# plantshield_huzzah_2022.net
KiCad netlist of a schematic drawn in EAGLE
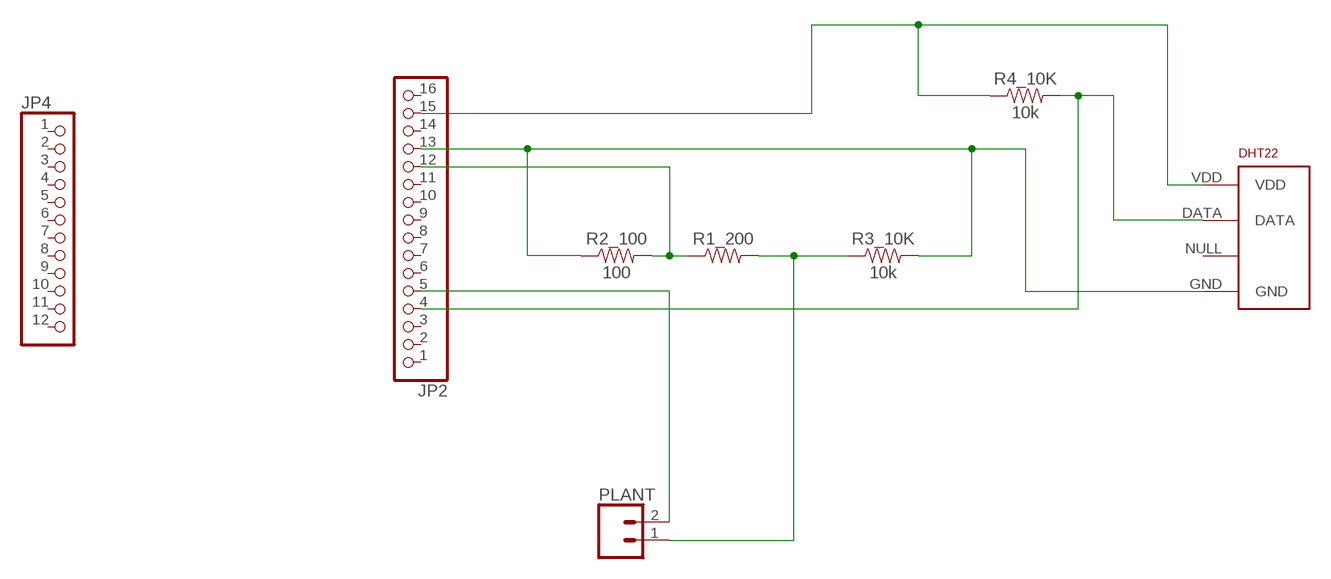
[diagram p0: schematic, sheet 1]

(export (version "E")
  (design (tool "Eeschema 10.0.6"))
  (components
    (comp (ref "DHT22")
      (value "RHT03_DHT-22_AM2302")
      (footprint "eagle-import:RHT03_DHT-22")
      (libsource (lib "eagle-import") (part "RHT03_DHT-22_AM2302"))
    )
    (comp (ref "JP2")
      (value "HEADER-1X16ROUND")
      (footprint "eagle-import:1X16_ROUND")
      (libsource (lib "eagle-import") (part "HEADER-1X16ROUND"))
    )
    (comp (ref "JP4")
      (value "HEADER-1X12")
      (footprint "eagle-import:1X12_ROUND")
      (libsource (lib "eagle-import") (part "HEADER-1X12"))
    )
    (comp (ref "PLANT")
      (value "CONN_02")
      (footprint "eagle-import:1X02")
      (libsource (lib "eagle-import") (part "CONN_02"))
    )
    (comp (ref "R1_200")
      (value "RESISTORAXIAL-0.3")
      (footprint "eagle-import:AXIAL-0.3")
      (libsource (lib "eagle-import") (part "RESISTORAXIAL-0.3"))
    )
    (comp (ref "R2_100")
      (value "100")
      (footprint "eagle-import:AXIAL-0.3")
      (libsource (lib "eagle-import") (part "100OHM-HORIZ-1/4W-1%"))
    )
    (comp (ref "R3_10K")
      (value "10k")
      (footprint "eagle-import:AXIAL-0.3")
      (libsource (lib "eagle-import") (part "10KOHM-HORIZ-1/4W-1%"))
    )
    (comp (ref "R4_10K")
      (value "10k")
      (footprint "eagle-import:AXIAL-0.3")
      (libsource (lib "eagle-import") (part "10KOHM-HORIZ-1/4W-1%"))
    )
  )
  (nets
    (net (code "1") (name "Net-(JP2-Pad5)") (class "Default")
      (node (ref "JP2") (pin "5") (pinfunction "5_5") (pintype "passive"))
      (node (ref "PLANT") (pin "2") (pinfunction "2_2") (pintype "passive"))
    )
    (net (code "2") (name "Net-(R1_200-1)") (class "Default")
      (node (ref "JP2") (pin "12") (pinfunction "12_12") (pintype "passive"))
      (node (ref "R1_200") (pin "P$1") (pinfunction "1_P$1") (pintype "passive"))
      (node (ref "R2_100") (pin "P$2") (pinfunction "2_P$2") (pintype "passive"))
    )
    (net (code "3") (name "Net-(R1_200-2)") (class "Default")
      (node (ref "PLANT") (pin "1") (pinfunction "1_1") (pintype "passive"))
      (node (ref "R1_200") (pin "P$2") (pinfunction "2_P$2") (pintype "passive"))
      (node (ref "R3_10K") (pin "P$1") (pinfunction "1_P$1") (pintype "passive"))
    )
    (net (code "4") (name "Net-(R2_100-1)") (class "Default")
      (node (ref "DHT22") (pin "GND") (pinfunction "GND_GND") (pintype "power_in"))
      (node (ref "JP2") (pin "13") (pinfunction "13_13") (pintype "passive"))
      (node (ref "R2_100") (pin "P$1") (pinfunction "1_P$1") (pintype "passive"))
      (node (ref "R3_10K") (pin "P$2") (pinfunction "2_P$2") (pintype "passive"))
    )
    (net (code "5") (name "Net-(R4_10K-1)") (class "Default")
      (node (ref "DHT22") (pin "VDD") (pinfunction "VDD_VDD") (pintype "power_in"))
      (node (ref "JP2") (pin "15") (pinfunction "15_15") (pintype "passive"))
      (node (ref "R4_10K") (pin "P$1") (pinfunction "1_P$1") (pintype "passive"))
    )
    (net (code "6") (name "Net-(R4_10K-2)") (class "Default")
      (node (ref "DHT22") (pin "DATA") (pinfunction "DATA_DATA") (pintype "bidirectional"))
      (node (ref "JP2") (pin "4") (pinfunction "4_4") (pintype "passive"))
      (node (ref "R4_10K") (pin "P$2") (pinfunction "2_P$2") (pintype "passive"))
    )
    (net (code "7") (name "unconnected-(DHT22-PadNULL)") (class "Default")
      (node (ref "DHT22") (pin "NULL") (pinfunction "NULL_NULL") (pintype "no_connect"))
    )
    (net (code "8") (name "unconnected-(JP2-Pad1)") (class "Default")
      (node (ref "JP2") (pin "1") (pinfunction "1_1") (pintype "passive"))
    )
    (net (code "9") (name "unconnected-(JP2-Pad2)") (class "Default")
      (node (ref "JP2") (pin "2") (pinfunction "2_2") (pintype "passive"))
    )
    (net (code "10") (name "unconnected-(JP2-Pad3)") (class "Default")
      (node (ref "JP2") (pin "3") (pinfunction "3_3") (pintype "passive"))
    )
    (net (code "11") (name "unconnected-(JP2-Pad6)") (class "Default")
      (node (ref "JP2") (pin "6") (pinfunction "6_6") (pintype "passive"))
    )
    (net (code "12") (name "unconnected-(JP2-Pad7)") (class "Default")
      (node (ref "JP2") (pin "7") (pinfunction "7_7") (pintype "passive"))
    )
    (net (code "13") (name "unconnected-(JP2-Pad8)") (class "Default")
      (node (ref "JP2") (pin "8") (pinfunction "8_8") (pintype "passive"))
    )
    (net (code "14") (name "unconnected-(JP2-Pad9)") (class "Default")
      (node (ref "JP2") (pin "9") (pinfunction "9_9") (pintype "passive"))
    )
    (net (code "15") (name "unconnected-(JP2-Pad10)") (class "Default")
      (node (ref "JP2") (pin "10") (pinfunction "10_10") (pintype "passive"))
    )
    (net (code "16") (name "unconnected-(JP2-Pad11)") (class "Default")
      (node (ref "JP2") (pin "11") (pinfunction "11_11") (pintype "passive"))
    )
    (net (code "17") (name "unconnected-(JP2-Pad14)") (class "Default")
      (node (ref "JP2") (pin "14") (pinfunction "14_14") (pintype "passive"))
    )
    (net (code "18") (name "unconnected-(JP2-Pad16)") (class "Default")
      (node (ref "JP2") (pin "16") (pinfunction "16_16") (pintype "passive"))
    )
    (net (code "19") (name "unconnected-(JP4-Pad1)") (class "Default")
      (node (ref "JP4") (pin "1") (pinfunction "1_1") (pintype "passive"))
    )
    (net (code "20") (name "unconnected-(JP4-Pad2)") (class "Default")
      (node (ref "JP4") (pin "2") (pinfunction "2_2") (pintype "passive"))
    )
    (net (code "21") (name "unconnected-(JP4-Pad3)") (class "Default")
      (node (ref "JP4") (pin "3") (pinfunction "3_3") (pintype "passive"))
    )
    (net (code "22") (name "unconnected-(JP4-Pad4)") (class "Default")
      (node (ref "JP4") (pin "4") (pinfunction "4_4") (pintype "passive"))
    )
    (net (code "23") (name "unconnected-(JP4-Pad5)") (class "Default")
      (node (ref "JP4") (pin "5") (pinfunction "5_5") (pintype "passive"))
    )
    (net (code "24") (name "unconnected-(JP4-Pad6)") (class "Default")
      (node (ref "JP4") (pin "6") (pinfunction "6_6") (pintype "passive"))
    )
    (net (code "25") (name "unconnected-(JP4-Pad7)") (class "Default")
      (node (ref "JP4") (pin "7") (pinfunction "7_7") (pintype "passive"))
    )
    (net (code "26") (name "unconnected-(JP4-Pad8)") (class "Default")
      (node (ref "JP4") (pin "8") (pinfunction "8_8") (pintype "passive"))
    )
    (net (code "27") (name "unconnected-(JP4-Pad9)") (class "Default")
      (node (ref "JP4") (pin "9") (pinfunction "9_9") (pintype "passive"))
    )
    (net (code "28") (name "unconnected-(JP4-Pad10)") (class "Default")
      (node (ref "JP4") (pin "10") (pinfunction "10_10") (pintype "passive"))
    )
    (net (code "29") (name "unconnected-(JP4-Pad11)") (class "Default")
      (node (ref "JP4") (pin "11") (pinfunction "11_11") (pintype "passive"))
    )
    (net (code "30") (name "unconnected-(JP4-Pad12)") (class "Default")
      (node (ref "JP4") (pin "12") (pinfunction "12_12") (pintype "passive"))
    )
  )
)
